# Wifi.net
KiCad netlist of a schematic drawn in Altium Designer
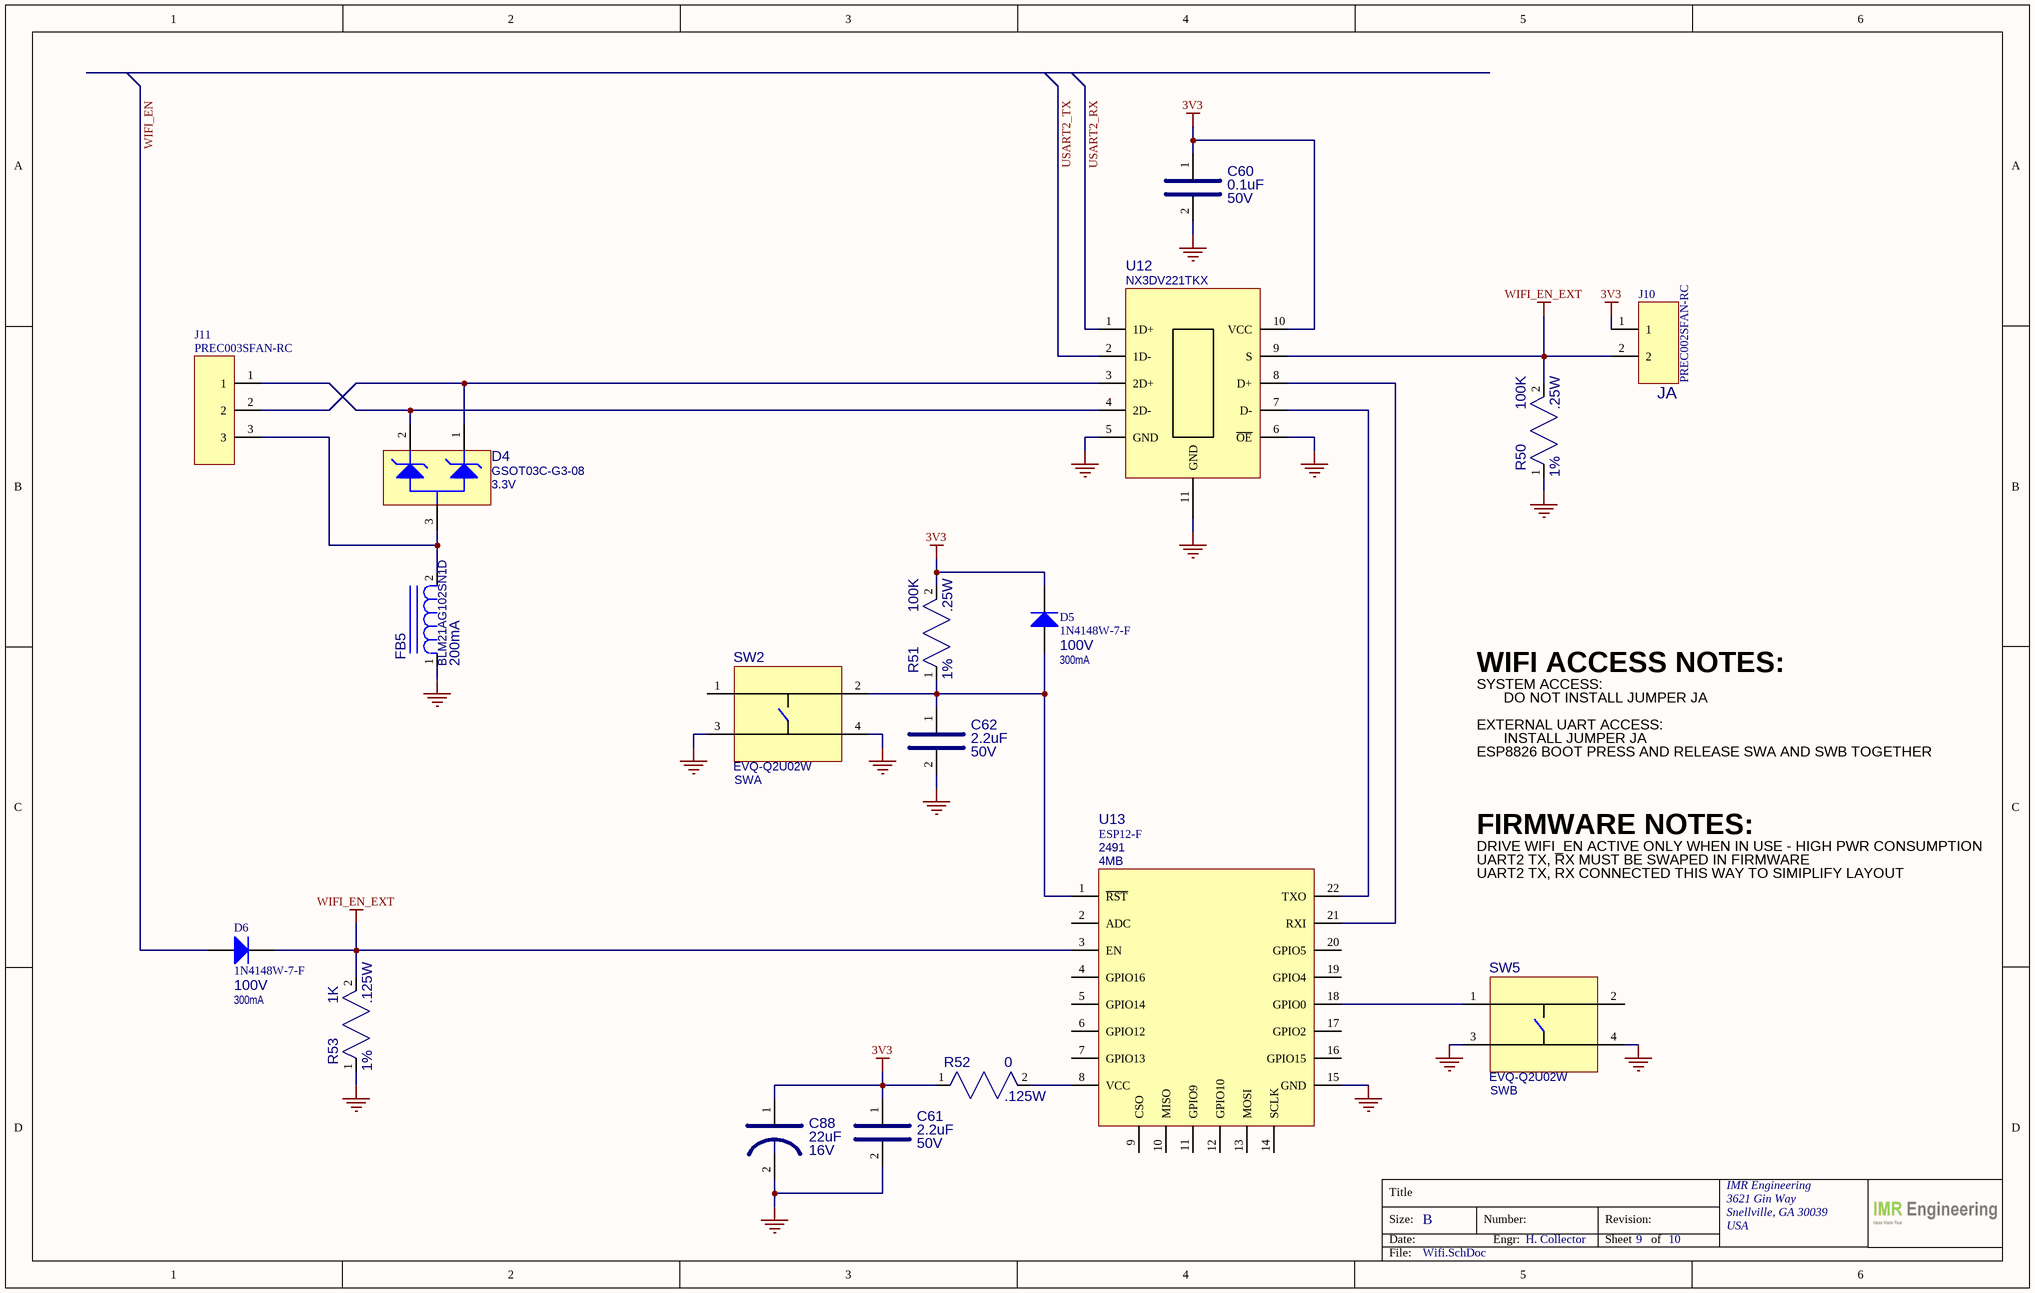
[diagram p0: Wifi.SchDoc]

(export (version "E")
  (design (tool "Eeschema 10.0.6"))
  (components
    (comp (ref "C60")
      (value "0.1uF")
      (footprint "CAP_0805")
      (description "CAP CER 0.1UF 50V X7R 0805")
      (fields (field (name "MFG") "AVX") (field (name "TOLERANCE") "10%") (field (name "VOLTAGE") "50V"))
      (libsource (lib "IMR_Lib") (part "CAP_0.1UF_50V_0805"))
    )
    (comp (ref "C61")
      (value "2.2uF")
      (footprint "CAP_0805")
      (description "CAP CER 2.2UF 50V X7R 0805")
      (fields
        (field (name "MFG") "Taiyo Yuden")
        (field (name "TOLERANCE") "20%")
        (field (name "VOLTAGE") "50V")
      )
      (libsource (lib "IMR_Lib") (part "CAP_2.2UF_50V_0805"))
    )
    (comp (ref "C62")
      (value "2.2uF")
      (footprint "CAP_0805")
      (description "CAP CER 2.2UF 50V X7R 0805")
      (fields
        (field (name "MFG") "Taiyo Yuden")
        (field (name "TOLERANCE") "20%")
        (field (name "VOLTAGE") "50V")
      )
      (libsource (lib "IMR_Lib") (part "CAP_2.2UF_50V_0805"))
    )
    (comp (ref "C88")
      (value "22uF")
      (footprint "CAP_2312")
      (description "CAP TANT 22UF 10% 16V 2312")
      (fields
        (field (name "MFG") "AVX Corporation")
        (field (name "TOLERANCE") "10%")
        (field (name "VOLTAGE") "16V")
      )
      (libsource (lib "IMR_Lib") (part "CAP_22UF_16V_TANT"))
    )
    (comp (ref "D4")
      (value "3.3V")
      (footprint "SOT-23")
      (description "TVS DIODE 3.3V 12.3V SOT23")
      (fields
        (field (name "MFG") "Vishay Semiconductor")
        (field (name "POWER") "30A (8/20us)")
        (field (name "MFG_PN") "GSOT03C-G3-08")
      )
      (libsource (lib "IMR_Lib") (part "DIODE_TVS_GSOT03C-G3-08"))
    )
    (comp (ref "D5")
      (value "100V")
      (footprint "SOD123")
      (description "DIODE GEN PURP 100V 300MA SOD123")
      (fields
        (field (name "MFG") "Diodes Incorporated")
        (field (name "MFG_PN") "1N4148W-7-F")
        (field (name "CURRENT") "300mA")
        (field (name "Comment") "1N4148W-7-F")
      )
      (libsource (lib "IMR_Lib") (part "DIODE_1N4148W-7-F"))
    )
    (comp (ref "D6")
      (value "100V")
      (footprint "SOD123")
      (description "DIODE GEN PURP 100V 300MA SOD123")
      (fields
        (field (name "MFG") "Diodes Incorporated")
        (field (name "MFG_PN") "1N4148W-7-F")
        (field (name "CURRENT") "300mA")
        (field (name "Comment") "1N4148W-7-F")
      )
      (libsource (lib "IMR_Lib") (part "DIODE_1N4148W-7-F"))
    )
    (comp (ref "FB5")
      (value "200mA")
      (footprint "RES_0805")
      (description "FERRITE, 1KOHM AT 100MHZ, 220MA, .450DCR")
      (fields
        (field (name "MFG") "MURATA")
        (field (name "TOLERANCE") "10%")
        (field (name "MFG_PN") "BLM21AG102SN1D")
      )
      (libsource (lib "IMR_Lib") (part "FERRITE_BLM21AG102SN1D"))
    )
    (comp (ref "J10")
      (value "PREC002SFAN-RC")
      (footprint "HDR_1X2_100MILL")
      (description "CONN HEADER VERT 2POS 2.54MM")
      (fields (field (name "MFG") "Sullins Connector Solutions") (field (name "OPERATION_NOTE") "JA"))
      (libsource (lib "IMR_Lib") (part "CONN_2P_SINGLE_ROW"))
    )
    (comp (ref "J11")
      (value "PREC003SFAN-RC")
      (footprint "HDR_1X3_100MILL")
      (description "CONN HEADER VERT 3POS 2.54MM")
      (fields (field (name "MFG") "Sullins Connector Solutions"))
      (libsource (lib "IMR_Lib") (part "CONN_3P_SINGLE_ROW"))
    )
    (comp (ref "R50")
      (value "100K")
      (footprint "PMG_RES_0805")
      (description "RES SMD 100K OHM 1% 1/4W 0805")
      (fields
        (field (name "MFG") "KOA Speer Electronics, Inc.")
        (field (name "TOLERANCE") "1%")
        (field (name "POWER") ".25W")
        (field (name "Comment") "RK73H2ATTD1003F")
      )
      (libsource (lib "IMR_Lib") (part "RES_100K_0805_1/4W_1%"))
    )
    (comp (ref "R51")
      (value "100K")
      (footprint "PMG_RES_0805")
      (description "RES SMD 100K OHM 1% 1/4W 0805")
      (fields
        (field (name "MFG") "KOA Speer Electronics, Inc.")
        (field (name "TOLERANCE") "1%")
        (field (name "POWER") ".25W")
        (field (name "Comment") "RK73H2ATTD1003F")
      )
      (libsource (lib "IMR_Lib") (part "RES_100K_0805_1/4W_1%"))
    )
    (comp (ref "R52")
      (value "0")
      (footprint "PMG_RES_0805")
      (description "RES SMD 0 OHM JUMPER 1/8W 0805")
      (fields (field (name "MFG") "Yageo") (field (name "TOLERANCE") "JUMPER") (field (name "POWER") ".125W"))
      (libsource (lib "IMR_Lib") (part "RES_0_0805_1/8W"))
    )
    (comp (ref "R53")
      (value "1K")
      (footprint "RES_0805")
      (description "RES SMD 1K OHM 1% 1/8W 0805")
      (fields
        (field (name "MFG") "Yageo")
        (field (name "TOLERANCE") "1%")
        (field (name "POWER") ".125W")
        (field (name "Comment") "RC0805FR-071KL")
      )
      (libsource (lib "IMR_Lib") (part "RES_1K_0805_1/8W_1%"))
    )
    (comp (ref "SW2")
      (value "EVQ-Q2U02W")
      (footprint "SW_EVQ-Q2U02W")
      (description "SWITCH TACTILE SPST-NO 0.02A 15V")
      (fields
        (field (name "MFG") "Panasonic Electronic Components")
        (field (name "MFG_PN") "EVQ-Q2U02W")
        (field (name "OPERATION_NOTE") "SWA")
      )
      (libsource (lib "IMR_Lib") (part "SWITCH_EVQ-Q2U02W"))
    )
    (comp (ref "SW5")
      (value "EVQ-Q2U02W")
      (footprint "SW_EVQ-Q2U02W")
      (description "SWITCH TACTILE SPST-NO 0.02A 15V")
      (fields
        (field (name "MFG") "Panasonic Electronic Components")
        (field (name "MFG_PN") "EVQ-Q2U02W")
        (field (name "OPERATION_NOTE") "SWB")
      )
      (libsource (lib "IMR_Lib") (part "SWITCH_EVQ-Q2U02W"))
    )
    (comp (ref "U12")
      (value "NX3DV221TKX")
      (footprint "PMG_NX3DV221TKX")
      (description "IC USB 2.0 SWITCH HS 10HVSON")
      (fields (field (name "MFG") "NXP USA Inc.") (field (name "MFG_PN") "NX3DV221TKX"))
      (libsource (lib "IMR_Lib") (part "IC_NX3DV221TKX"))
    )
    (comp (ref "U13")
      (value "2491")
      (footprint "XCVR_ESP8266-12E/ESP-12E")
      (description "RX TXRX MOD WIFI TRACE ANT SMD 4MB")
      (fields
        (field (name "MFG") "Adafruit Industries LLC")
        (field (name "PACKAGE") "ESP12-F")
        (field (name "MFG_PN") "2491")
        (field (name "FLASH") "4MB")
      )
      (libsource (lib "IMR_Lib") (part "MODULE_2491"))
    )
  )
  (nets
    (net (code "1") (name "/USART2_RX") (class "Default")
      (node (ref "U12") (pin "1") (pinfunction "1D+_1") (pintype "passive"))
    )
    (net (code "2") (name "/USART2_TX") (class "Default")
      (node (ref "U12") (pin "2") (pinfunction "1D-_2") (pintype "passive"))
    )
    (net (code "3") (name "/WIFI_EN") (class "Default")
      (node (ref "D6") (pin "1") (pinfunction "A_1") (pintype "passive"))
    )
    (net (code "4") (name "3V3") (class "Default")
      (node (ref "C60") (pin "1") (pinfunction "1_1") (pintype "passive"))
      (node (ref "C61") (pin "1") (pinfunction "1_1") (pintype "passive"))
      (node (ref "C88") (pin "1") (pinfunction "1_1") (pintype "passive"))
      (node (ref "D5") (pin "2") (pinfunction "K_2") (pintype "passive"))
      (node (ref "J10") (pin "1") (pinfunction "1_1") (pintype "passive"))
      (node (ref "R51") (pin "2") (pinfunction "2_2") (pintype "passive"))
      (node (ref "R52") (pin "1") (pinfunction "1_1") (pintype "passive"))
      (node (ref "U12") (pin "10") (pinfunction "VCC_10") (pintype "passive"))
    )
    (net (code "5") (name "GND") (class "Default")
      (node (ref "C60") (pin "2") (pinfunction "2_2") (pintype "passive"))
      (node (ref "C61") (pin "2") (pinfunction "2_2") (pintype "passive"))
      (node (ref "C62") (pin "2") (pinfunction "2_2") (pintype "passive"))
      (node (ref "C88") (pin "2") (pinfunction "2_2") (pintype "passive"))
      (node (ref "FB5") (pin "1") (pinfunction "1_1") (pintype "passive"))
      (node (ref "R50") (pin "1") (pinfunction "1_1") (pintype "passive"))
      (node (ref "R53") (pin "1") (pinfunction "1_1") (pintype "passive"))
      (node (ref "SW2") (pin "3") (pinfunction "A_3") (pintype "passive"))
      (node (ref "SW2") (pin "4") (pinfunction "A'_4") (pintype "passive"))
      (node (ref "SW5") (pin "3") (pinfunction "A_3") (pintype "passive"))
      (node (ref "SW5") (pin "4") (pinfunction "A'_4") (pintype "passive"))
      (node (ref "U12") (pin "11") (pinfunction "GND_11") (pintype "passive"))
      (node (ref "U12") (pin "5") (pinfunction "GND_5") (pintype "passive"))
      (node (ref "U12") (pin "6") (pinfunction "OE_6") (pintype "passive"))
      (node (ref "U13") (pin "15") (pinfunction "GND_15") (pintype "passive"))
    )
    (net (code "6") (name "Net-(D4-A)") (class "Default")
      (node (ref "D4") (pin "3") (pinfunction "A_3") (pintype "passive"))
      (node (ref "FB5") (pin "2") (pinfunction "2_2") (pintype "passive"))
      (node (ref "J11") (pin "3") (pinfunction "3_3") (pintype "passive"))
    )
    (net (code "7") (name "Net-(D4-A1)") (class "Default")
      (node (ref "D4") (pin "1") (pinfunction "A1_1") (pintype "passive"))
      (node (ref "J11") (pin "2") (pinfunction "2_2") (pintype "passive"))
      (node (ref "U12") (pin "3") (pinfunction "2D+_3") (pintype "passive"))
    )
    (net (code "8") (name "Net-(D4-A2)") (class "Default")
      (node (ref "D4") (pin "2") (pinfunction "A2_2") (pintype "passive"))
      (node (ref "J11") (pin "1") (pinfunction "1_1") (pintype "passive"))
      (node (ref "U12") (pin "4") (pinfunction "2D-_4") (pintype "passive"))
    )
    (net (code "9") (name "Net-(D5-A)") (class "Default")
      (node (ref "C62") (pin "1") (pinfunction "1_1") (pintype "passive"))
      (node (ref "D5") (pin "1") (pinfunction "A_1") (pintype "passive"))
      (node (ref "R51") (pin "1") (pinfunction "1_1") (pintype "passive"))
      (node (ref "SW2") (pin "2") (pinfunction "B'_2") (pintype "passive"))
      (node (ref "U13") (pin "1") (pinfunction "RST_1") (pintype "passive"))
    )
    (net (code "10") (name "Net-(SW5-B)") (class "Default")
      (node (ref "SW5") (pin "1") (pinfunction "B_1") (pintype "passive"))
      (node (ref "U13") (pin "18") (pinfunction "GPIO0_18") (pintype "passive"))
    )
    (net (code "11") (name "Net-(U12-D+)") (class "Default")
      (node (ref "U12") (pin "8") (pinfunction "D+_8") (pintype "passive"))
      (node (ref "U13") (pin "21") (pinfunction "RXI_21") (pintype "passive"))
    )
    (net (code "12") (name "Net-(U12-D-)") (class "Default")
      (node (ref "U12") (pin "7") (pinfunction "D-_7") (pintype "passive"))
      (node (ref "U13") (pin "22") (pinfunction "TXO_22") (pintype "passive"))
    )
    (net (code "13") (name "Net-(U13-VCC)") (class "Default")
      (node (ref "R52") (pin "2") (pinfunction "2_2") (pintype "passive"))
      (node (ref "U13") (pin "8") (pinfunction "VCC_8") (pintype "passive"))
    )
    (net (code "14") (name "WIFI_EN_EXT") (class "Default")
      (node (ref "D6") (pin "2") (pinfunction "K_2") (pintype "passive"))
      (node (ref "J10") (pin "2") (pinfunction "2_2") (pintype "passive"))
      (node (ref "R50") (pin "2") (pinfunction "2_2") (pintype "passive"))
      (node (ref "R53") (pin "2") (pinfunction "2_2") (pintype "passive"))
      (node (ref "U12") (pin "9") (pinfunction "S_9") (pintype "passive"))
      (node (ref "U13") (pin "3") (pinfunction "EN_3") (pintype "passive"))
    )
    (net (code "15") (name "unconnected-(SW2-B-Pad1)") (class "Default")
      (node (ref "SW2") (pin "1") (pinfunction "B_1") (pintype "passive"))
    )
    (net (code "16") (name "unconnected-(SW5-B'-Pad2)") (class "Default")
      (node (ref "SW5") (pin "2") (pinfunction "B'_2") (pintype "passive"))
    )
    (net (code "17") (name "unconnected-(U13-ADC-Pad2)") (class "Default")
      (node (ref "U13") (pin "2") (pinfunction "ADC_2") (pintype "passive"))
    )
    (net (code "18") (name "unconnected-(U13-CSO-Pad9)") (class "Default")
      (node (ref "U13") (pin "9") (pinfunction "CSO_9") (pintype "passive"))
    )
    (net (code "19") (name "unconnected-(U13-GPIO2-Pad17)") (class "Default")
      (node (ref "U13") (pin "17") (pinfunction "GPIO2_17") (pintype "passive"))
    )
    (net (code "20") (name "unconnected-(U13-GPIO4-Pad19)") (class "Default")
      (node (ref "U13") (pin "19") (pinfunction "GPIO4_19") (pintype "passive"))
    )
    (net (code "21") (name "unconnected-(U13-GPIO5-Pad20)") (class "Default")
      (node (ref "U13") (pin "20") (pinfunction "GPIO5_20") (pintype "passive"))
    )
    (net (code "22") (name "unconnected-(U13-GPIO9-Pad11)") (class "Default")
      (node (ref "U13") (pin "11") (pinfunction "GPIO9_11") (pintype "passive"))
    )
    (net (code "23") (name "unconnected-(U13-GPIO10-Pad12)") (class "Default")
      (node (ref "U13") (pin "12") (pinfunction "GPIO10_12") (pintype "passive"))
    )
    (net (code "24") (name "unconnected-(U13-GPIO12-Pad6)") (class "Default")
      (node (ref "U13") (pin "6") (pinfunction "GPIO12_6") (pintype "passive"))
    )
    (net (code "25") (name "unconnected-(U13-GPIO13-Pad7)") (class "Default")
      (node (ref "U13") (pin "7") (pinfunction "GPIO13_7") (pintype "passive"))
    )
    (net (code "26") (name "unconnected-(U13-GPIO14-Pad5)") (class "Default")
      (node (ref "U13") (pin "5") (pinfunction "GPIO14_5") (pintype "passive"))
    )
    (net (code "27") (name "unconnected-(U13-GPIO15-Pad16)") (class "Default")
      (node (ref "U13") (pin "16") (pinfunction "GPIO15_16") (pintype "passive"))
    )
    (net (code "28") (name "unconnected-(U13-GPIO16-Pad4)") (class "Default")
      (node (ref "U13") (pin "4") (pinfunction "GPIO16_4") (pintype "passive"))
    )
    (net (code "29") (name "unconnected-(U13-MISO-Pad10)") (class "Default")
      (node (ref "U13") (pin "10") (pinfunction "MISO_10") (pintype "passive"))
    )
    (net (code "30") (name "unconnected-(U13-MOSI-Pad13)") (class "Default")
      (node (ref "U13") (pin "13") (pinfunction "MOSI_13") (pintype "passive"))
    )
    (net (code "31") (name "unconnected-(U13-SCLK-Pad14)") (class "Default")
      (node (ref "U13") (pin "14") (pinfunction "SCLK_14") (pintype "passive"))
    )
  )
)
